# foo1.net
KiCad netlist of a schematic drawn in EAGLE
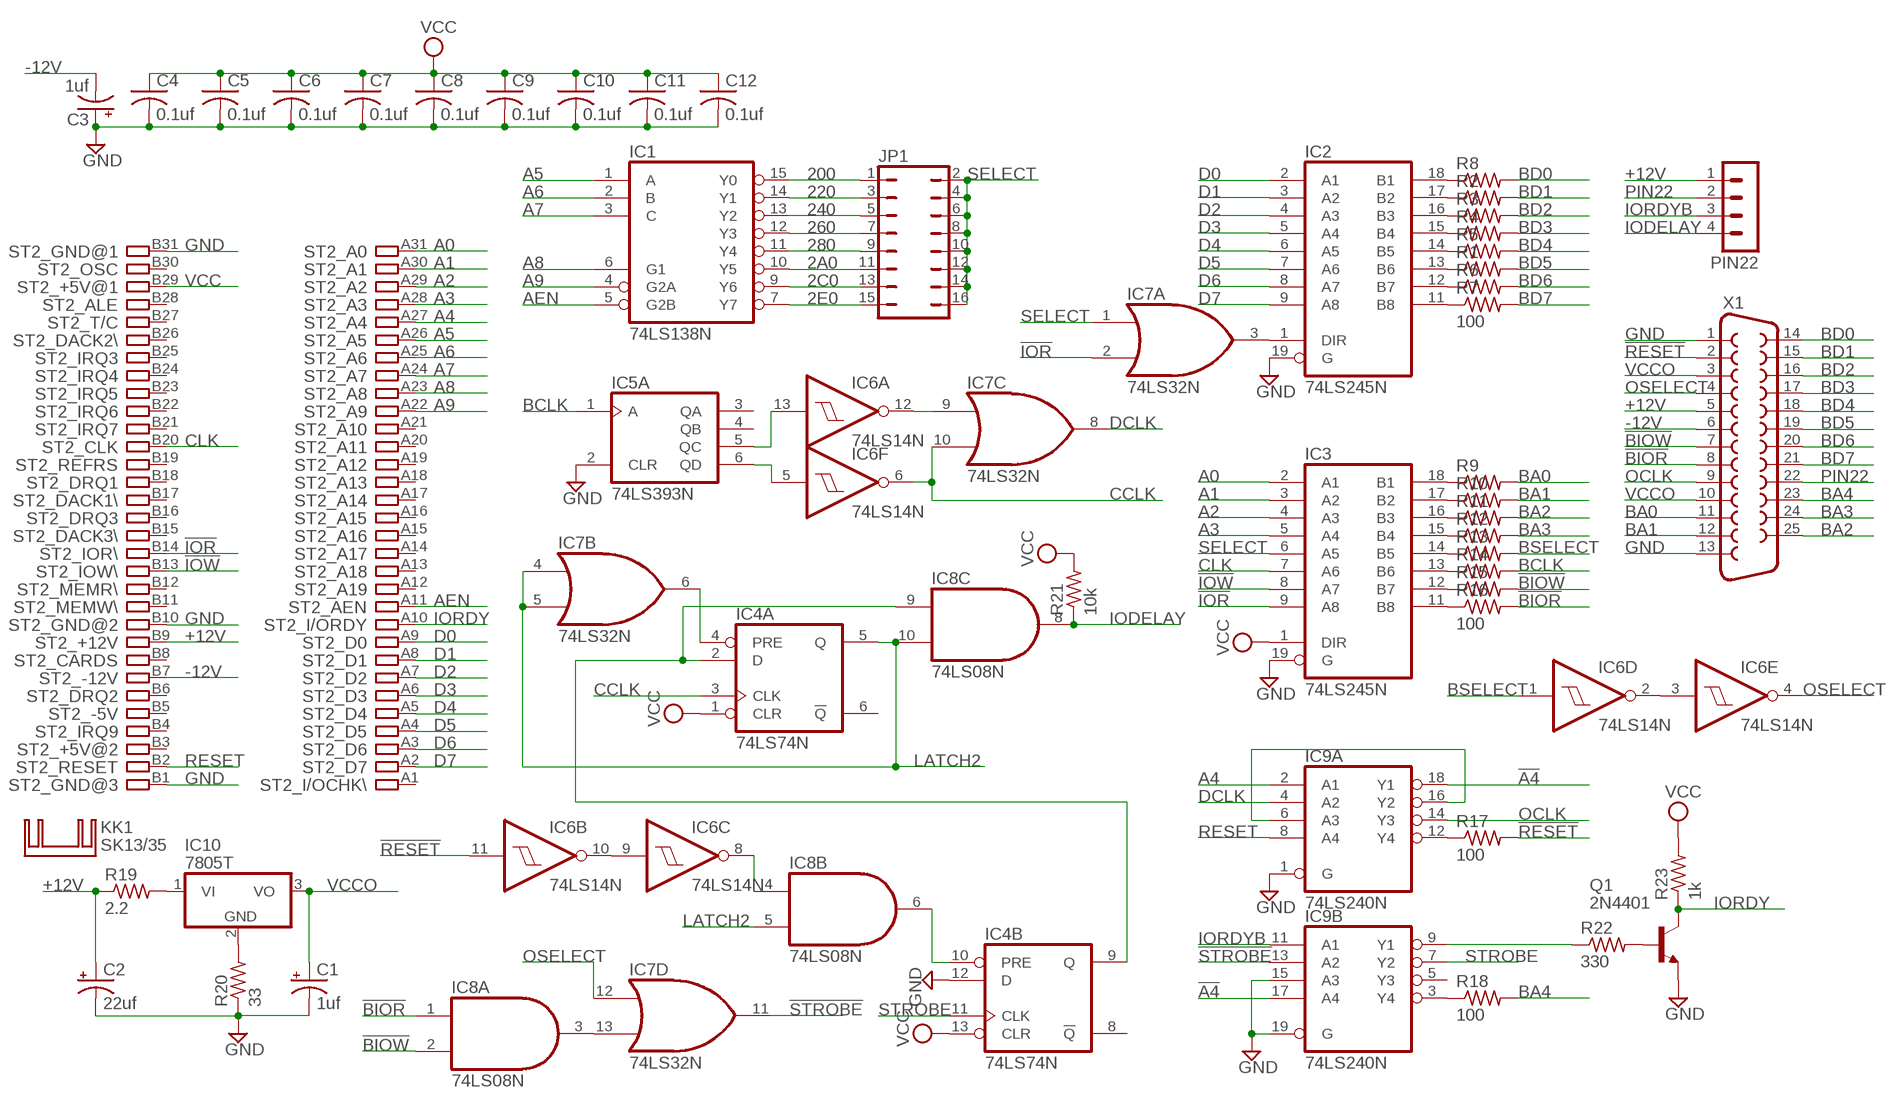
[diagram p0: schematic, sheet 1]

(export (version "E")
  (design (tool "Eeschema 10.0.6"))
  (components
    (comp (ref "C1")
      (value "1uf")
      (footprint "eagle-import:E5-10,5")
      (libsource (lib "eagle-import") (part "CPOL-USE5-10.5"))
    )
    (comp (ref "C2")
      (value "22uf")
      (footprint "eagle-import:E5-10,5")
      (libsource (lib "eagle-import") (part "CPOL-USE5-10.5"))
    )
    (comp (ref "C3")
      (value "1uf")
      (footprint "eagle-import:E5-10,5")
      (libsource (lib "eagle-import") (part "CPOL-USE5-10.5"))
    )
    (comp (ref "C4")
      (value "0.1uf")
      (footprint "eagle-import:C050-025X075")
      (libsource (lib "eagle-import") (part "C-US050-025X075"))
    )
    (comp (ref "C5")
      (value "0.1uf")
      (footprint "eagle-import:C050-025X075")
      (libsource (lib "eagle-import") (part "C-US050-025X075"))
    )
    (comp (ref "C6")
      (value "0.1uf")
      (footprint "eagle-import:C050-025X075")
      (libsource (lib "eagle-import") (part "C-US050-025X075"))
    )
    (comp (ref "C7")
      (value "0.1uf")
      (footprint "eagle-import:C050-025X075")
      (libsource (lib "eagle-import") (part "C-US050-025X075"))
    )
    (comp (ref "C8")
      (value "0.1uf")
      (footprint "eagle-import:C050-025X075")
      (libsource (lib "eagle-import") (part "C-US050-025X075"))
    )
    (comp (ref "C9")
      (value "0.1uf")
      (footprint "eagle-import:C050-025X075")
      (libsource (lib "eagle-import") (part "C-US050-025X075"))
    )
    (comp (ref "C10")
      (value "0.1uf")
      (footprint "eagle-import:C050-025X075")
      (libsource (lib "eagle-import") (part "C-US050-025X075"))
    )
    (comp (ref "C11")
      (value "0.1uf")
      (footprint "eagle-import:C050-025X075")
      (libsource (lib "eagle-import") (part "C-US050-025X075"))
    )
    (comp (ref "C12")
      (value "0.1uf")
      (footprint "eagle-import:C050-025X075")
      (libsource (lib "eagle-import") (part "C-US050-025X075"))
    )
    (comp (ref "IC1")
      (value "74LS138N")
      (footprint "eagle-import:DIL16")
      (libsource (lib "eagle-import") (part "74138NLS"))
    )
    (comp (ref "IC2")
      (value "74LS245N")
      (footprint "eagle-import:DIL20")
      (libsource (lib "eagle-import") (part "74245NLS"))
    )
    (comp (ref "IC3")
      (value "74LS245N")
      (footprint "eagle-import:DIL20")
      (libsource (lib "eagle-import") (part "74245NLS"))
    )
    (comp (ref "IC4")
      (value "74LS74N")
      (footprint "eagle-import:DIL14")
      (libsource (lib "eagle-import") (part "7474NLS"))
    )
    (comp (ref "IC5")
      (value "74LS393N")
      (footprint "eagle-import:DIL14")
      (libsource (lib "eagle-import") (part "74393NLS"))
    )
    (comp (ref "IC6")
      (value "74LS14N")
      (footprint "eagle-import:DIL14")
      (libsource (lib "eagle-import") (part "7414NLS"))
    )
    (comp (ref "IC7")
      (value "74LS32N")
      (footprint "eagle-import:DIL14")
      (libsource (lib "eagle-import") (part "7432NLS"))
    )
    (comp (ref "IC8")
      (value "74LS08N")
      (footprint "eagle-import:DIL14")
      (libsource (lib "eagle-import") (part "7408NLS"))
    )
    (comp (ref "IC9")
      (value "74LS240N")
      (footprint "eagle-import:DIL20")
      (libsource (lib "eagle-import") (part "74240NLS"))
    )
    (comp (ref "IC10")
      (value "7805T")
      (footprint "eagle-import:TO220H")
      (libsource (lib "eagle-import") (part "78T05"))
    )
    (comp (ref "JP1")
      (value "JP8Q")
      (footprint "eagle-import:JP8Q")
      (libsource (lib "eagle-import") (part "JP8Q"))
    )
    (comp (ref "KK1")
      (value "SK13/35")
      (footprint "eagle-import:SK13_35")
      (libsource (lib "eagle-import") (part "SK13/35"))
    )
    (comp (ref "PIN22")
      (value "MA04-1")
      (footprint "eagle-import:MA04-1")
      (libsource (lib "eagle-import") (part "MA04-1"))
    )
    (comp (ref "Q1")
      (value "2N4401")
      (footprint "eagle-import:TO92")
      (libsource (lib "eagle-import") (part "2N4416"))
    )
    (comp (ref "R1")
      (value "R-US_0207/10")
      (footprint "eagle-import:0207_10")
      (libsource (lib "eagle-import") (part "R-US_0207/10"))
    )
    (comp (ref "R2")
      (value "R-US_0207/10")
      (footprint "eagle-import:0207_10")
      (libsource (lib "eagle-import") (part "R-US_0207/10"))
    )
    (comp (ref "R3")
      (value "R-US_0207/10")
      (footprint "eagle-import:0207_10")
      (libsource (lib "eagle-import") (part "R-US_0207/10"))
    )
    (comp (ref "R4")
      (value "R-US_0207/10")
      (footprint "eagle-import:0207_10")
      (libsource (lib "eagle-import") (part "R-US_0207/10"))
    )
    (comp (ref "R5")
      (value "R-US_0207/10")
      (footprint "eagle-import:0207_10")
      (libsource (lib "eagle-import") (part "R-US_0207/10"))
    )
    (comp (ref "R6")
      (value "R-US_0207/10")
      (footprint "eagle-import:0207_10")
      (libsource (lib "eagle-import") (part "R-US_0207/10"))
    )
    (comp (ref "R7")
      (value "100")
      (footprint "eagle-import:0207_10")
      (libsource (lib "eagle-import") (part "R-US_0207/10"))
    )
    (comp (ref "R8")
      (value "R-US_0207/10")
      (footprint "eagle-import:0207_10")
      (libsource (lib "eagle-import") (part "R-US_0207/10"))
    )
    (comp (ref "R9")
      (value "R-US_0207/10")
      (footprint "eagle-import:0207_10")
      (libsource (lib "eagle-import") (part "R-US_0207/10"))
    )
    (comp (ref "R10")
      (value "R-US_0207/10")
      (footprint "eagle-import:0207_10")
      (libsource (lib "eagle-import") (part "R-US_0207/10"))
    )
    (comp (ref "R11")
      (value "R-US_0207/10")
      (footprint "eagle-import:0207_10")
      (libsource (lib "eagle-import") (part "R-US_0207/10"))
    )
    (comp (ref "R12")
      (value "R-US_0207/10")
      (footprint "eagle-import:0207_10")
      (libsource (lib "eagle-import") (part "R-US_0207/10"))
    )
    (comp (ref "R13")
      (value "R-US_0207/10")
      (footprint "eagle-import:0207_10")
      (libsource (lib "eagle-import") (part "R-US_0207/10"))
    )
    (comp (ref "R14")
      (value "R-US_0207/10")
      (footprint "eagle-import:0207_10")
      (libsource (lib "eagle-import") (part "R-US_0207/10"))
    )
    (comp (ref "R15")
      (value "R-US_0207/10")
      (footprint "eagle-import:0207_10")
      (libsource (lib "eagle-import") (part "R-US_0207/10"))
    )
    (comp (ref "R16")
      (value "100")
      (footprint "eagle-import:0207_10")
      (libsource (lib "eagle-import") (part "R-US_0207/10"))
    )
    (comp (ref "R17")
      (value "100")
      (footprint "eagle-import:0207_10")
      (libsource (lib "eagle-import") (part "R-US_0207/10"))
    )
    (comp (ref "R18")
      (value "100")
      (footprint "eagle-import:0207_10")
      (libsource (lib "eagle-import") (part "R-US_0207/10"))
    )
    (comp (ref "R19")
      (value "2.2")
      (footprint "eagle-import:P0613_15")
      (libsource (lib "eagle-import") (part "R-US_0613/15"))
    )
    (comp (ref "R20")
      (value "33")
      (footprint "eagle-import:0207_10")
      (libsource (lib "eagle-import") (part "R-US_0207/10"))
    )
    (comp (ref "R21")
      (value "10k")
      (footprint "eagle-import:0207_10")
      (libsource (lib "eagle-import") (part "R-US_0207/10"))
    )
    (comp (ref "R22")
      (value "330")
      (footprint "eagle-import:0207_10")
      (libsource (lib "eagle-import") (part "R-US_0207/10"))
    )
    (comp (ref "R23")
      (value "1k")
      (footprint "eagle-import:0207_10")
      (libsource (lib "eagle-import") (part "R-US_0207/10"))
    )
    (comp (ref "ST2")
      (value "IBM8BIT")
      (footprint "eagle-import:IBM8BIT")
      (libsource (lib "eagle-import") (part "IBM8BIT"))
    )
    (comp (ref "X1")
      (value "F25H")
      (footprint "eagle-import:F25H")
      (libsource (lib "eagle-import") (part "F25H"))
    )
  )
  (nets
    (net (code "1") (name "/+12V") (class "Default")
      (node (ref "C2") (pin "+") (pinfunction "+_+") (pintype "passive"))
      (node (ref "PIN22") (pin "1") (pinfunction "1_1") (pintype "passive"))
      (node (ref "R19") (pin "1") (pinfunction "1_1") (pintype "passive"))
      (node (ref "ST2") (pin "B9") (pinfunction "P_B9") (pintype "bidirectional"))
      (node (ref "X1") (pin "5") (pinfunction "5_5") (pintype "passive"))
    )
    (net (code "2") (name "/-12V") (class "Default")
      (node (ref "C3") (pin "-") (pinfunction "-_-") (pintype "passive"))
      (node (ref "ST2") (pin "B7") (pinfunction "P_B7") (pintype "bidirectional"))
      (node (ref "X1") (pin "6") (pinfunction "6_6") (pintype "passive"))
    )
    (net (code "3") (name "/2A0") (class "Default")
      (node (ref "IC1") (pin "10") (pinfunction "Y5_10") (pintype "output"))
      (node (ref "JP1") (pin "11") (pinfunction "11_11") (pintype "passive"))
    )
    (net (code "4") (name "/2C0") (class "Default")
      (node (ref "IC1") (pin "9") (pinfunction "Y6_9") (pintype "output"))
      (node (ref "JP1") (pin "13") (pinfunction "13_13") (pintype "passive"))
    )
    (net (code "5") (name "/2E0") (class "Default")
      (node (ref "IC1") (pin "7") (pinfunction "Y7_7") (pintype "output"))
      (node (ref "JP1") (pin "15") (pinfunction "15_15") (pintype "passive"))
    )
    (net (code "6") (name "/200") (class "Default")
      (node (ref "IC1") (pin "15") (pinfunction "Y0_15") (pintype "output"))
      (node (ref "JP1") (pin "1") (pinfunction "1_1") (pintype "passive"))
    )
    (net (code "7") (name "/220") (class "Default")
      (node (ref "IC1") (pin "14") (pinfunction "Y1_14") (pintype "output"))
      (node (ref "JP1") (pin "3") (pinfunction "3_3") (pintype "passive"))
    )
    (net (code "8") (name "/240") (class "Default")
      (node (ref "IC1") (pin "13") (pinfunction "Y2_13") (pintype "output"))
      (node (ref "JP1") (pin "5") (pinfunction "5_5") (pintype "passive"))
    )
    (net (code "9") (name "/260") (class "Default")
      (node (ref "IC1") (pin "12") (pinfunction "Y3_12") (pintype "output"))
      (node (ref "JP1") (pin "7") (pinfunction "7_7") (pintype "passive"))
    )
    (net (code "10") (name "/280") (class "Default")
      (node (ref "IC1") (pin "11") (pinfunction "Y4_11") (pintype "output"))
      (node (ref "JP1") (pin "9") (pinfunction "9_9") (pintype "passive"))
    )
    (net (code "11") (name "/A0") (class "Default")
      (node (ref "IC3") (pin "2") (pinfunction "A1_2") (pintype "bidirectional"))
      (node (ref "ST2") (pin "A31") (pinfunction "P_A31") (pintype "bidirectional"))
    )
    (net (code "12") (name "/A1") (class "Default")
      (node (ref "IC3") (pin "3") (pinfunction "A2_3") (pintype "bidirectional"))
      (node (ref "ST2") (pin "A30") (pinfunction "P_A30") (pintype "bidirectional"))
    )
    (net (code "13") (name "/A2") (class "Default")
      (node (ref "IC3") (pin "4") (pinfunction "A3_4") (pintype "bidirectional"))
      (node (ref "ST2") (pin "A29") (pinfunction "P_A29") (pintype "bidirectional"))
    )
    (net (code "14") (name "/A3") (class "Default")
      (node (ref "IC3") (pin "5") (pinfunction "A4_5") (pintype "bidirectional"))
      (node (ref "ST2") (pin "A28") (pinfunction "P_A28") (pintype "bidirectional"))
    )
    (net (code "15") (name "/A4") (class "Default")
      (node (ref "IC9") (pin "2") (pinfunction "A1_2") (pintype "input"))
      (node (ref "ST2") (pin "A27") (pinfunction "P_A27") (pintype "bidirectional"))
    )
    (net (code "16") (name "/A5") (class "Default")
      (node (ref "IC1") (pin "1") (pinfunction "A_1") (pintype "input"))
      (node (ref "ST2") (pin "A26") (pinfunction "P_A26") (pintype "bidirectional"))
    )
    (net (code "17") (name "/A6") (class "Default")
      (node (ref "IC1") (pin "2") (pinfunction "B_2") (pintype "input"))
      (node (ref "ST2") (pin "A25") (pinfunction "P_A25") (pintype "bidirectional"))
    )
    (net (code "18") (name "/A7") (class "Default")
      (node (ref "IC1") (pin "3") (pinfunction "C_3") (pintype "input"))
      (node (ref "ST2") (pin "A24") (pinfunction "P_A24") (pintype "bidirectional"))
    )
    (net (code "19") (name "/A8") (class "Default")
      (node (ref "IC1") (pin "6") (pinfunction "G1_6") (pintype "input"))
      (node (ref "ST2") (pin "A23") (pinfunction "P_A23") (pintype "bidirectional"))
    )
    (net (code "20") (name "/A9") (class "Default")
      (node (ref "IC1") (pin "4") (pinfunction "G2A_4") (pintype "input"))
      (node (ref "ST2") (pin "A22") (pinfunction "P_A22") (pintype "bidirectional"))
    )
    (net (code "21") (name "/AEN") (class "Default")
      (node (ref "IC1") (pin "5") (pinfunction "G2B_5") (pintype "input"))
      (node (ref "ST2") (pin "A11") (pinfunction "P_A11") (pintype "bidirectional"))
    )
    (net (code "22") (name "/BA0") (class "Default")
      (node (ref "R9") (pin "2") (pinfunction "2_2") (pintype "passive"))
      (node (ref "X1") (pin "11") (pinfunction "11_11") (pintype "passive"))
    )
    (net (code "23") (name "/BA1") (class "Default")
      (node (ref "R10") (pin "2") (pinfunction "2_2") (pintype "passive"))
      (node (ref "X1") (pin "12") (pinfunction "12_12") (pintype "passive"))
    )
    (net (code "24") (name "/BA2") (class "Default")
      (node (ref "R11") (pin "2") (pinfunction "2_2") (pintype "passive"))
      (node (ref "X1") (pin "25") (pinfunction "25_25") (pintype "passive"))
    )
    (net (code "25") (name "/BA3") (class "Default")
      (node (ref "R12") (pin "2") (pinfunction "2_2") (pintype "passive"))
      (node (ref "X1") (pin "24") (pinfunction "24_24") (pintype "passive"))
    )
    (net (code "26") (name "/BA4") (class "Default")
      (node (ref "R18") (pin "2") (pinfunction "2_2") (pintype "passive"))
      (node (ref "X1") (pin "23") (pinfunction "23_23") (pintype "passive"))
    )
    (net (code "27") (name "/BCLK") (class "Default")
      (node (ref "IC5") (pin "1") (pinfunction "A_1") (pintype "input"))
      (node (ref "R14") (pin "2") (pinfunction "2_2") (pintype "passive"))
    )
    (net (code "28") (name "/BD0") (class "Default")
      (node (ref "R8") (pin "2") (pinfunction "2_2") (pintype "passive"))
      (node (ref "X1") (pin "14") (pinfunction "14_14") (pintype "passive"))
    )
    (net (code "29") (name "/BD1") (class "Default")
      (node (ref "R2") (pin "2") (pinfunction "2_2") (pintype "passive"))
      (node (ref "X1") (pin "15") (pinfunction "15_15") (pintype "passive"))
    )
    (net (code "30") (name "/BD2") (class "Default")
      (node (ref "R3") (pin "2") (pinfunction "2_2") (pintype "passive"))
      (node (ref "X1") (pin "16") (pinfunction "16_16") (pintype "passive"))
    )
    (net (code "31") (name "/BD3") (class "Default")
      (node (ref "R4") (pin "2") (pinfunction "2_2") (pintype "passive"))
      (node (ref "X1") (pin "17") (pinfunction "17_17") (pintype "passive"))
    )
    (net (code "32") (name "/BD4") (class "Default")
      (node (ref "R5") (pin "2") (pinfunction "2_2") (pintype "passive"))
      (node (ref "X1") (pin "18") (pinfunction "18_18") (pintype "passive"))
    )
    (net (code "33") (name "/BD5") (class "Default")
      (node (ref "R1") (pin "2") (pinfunction "2_2") (pintype "passive"))
      (node (ref "X1") (pin "19") (pinfunction "19_19") (pintype "passive"))
    )
    (net (code "34") (name "/BD6") (class "Default")
      (node (ref "R6") (pin "2") (pinfunction "2_2") (pintype "passive"))
      (node (ref "X1") (pin "20") (pinfunction "20_20") (pintype "passive"))
    )
    (net (code "35") (name "/BD7") (class "Default")
      (node (ref "R7") (pin "2") (pinfunction "2_2") (pintype "passive"))
      (node (ref "X1") (pin "21") (pinfunction "21_21") (pintype "passive"))
    )
    (net (code "36") (name "/BSELECT") (class "Default")
      (node (ref "IC6") (pin "1") (pinfunction "I_1") (pintype "input"))
      (node (ref "R13") (pin "2") (pinfunction "2_2") (pintype "passive"))
    )
    (net (code "37") (name "/CCLK") (class "Default")
      (node (ref "IC4") (pin "3") (pinfunction "CLK_3") (pintype "input"))
      (node (ref "IC6") (pin "6") (pinfunction "O_6") (pintype "output"))
      (node (ref "IC7") (pin "10") (pinfunction "I1_10") (pintype "input"))
    )
    (net (code "38") (name "/CLK") (class "Default")
      (node (ref "IC3") (pin "7") (pinfunction "A6_7") (pintype "bidirectional"))
      (node (ref "ST2") (pin "B20") (pinfunction "P_B20") (pintype "bidirectional"))
    )
    (net (code "39") (name "/D0") (class "Default")
      (node (ref "IC2") (pin "2") (pinfunction "A1_2") (pintype "bidirectional"))
      (node (ref "ST2") (pin "A9") (pinfunction "P_A9") (pintype "bidirectional"))
    )
    (net (code "40") (name "/D1") (class "Default")
      (node (ref "IC2") (pin "3") (pinfunction "A2_3") (pintype "bidirectional"))
      (node (ref "ST2") (pin "A8") (pinfunction "P_A8") (pintype "bidirectional"))
    )
    (net (code "41") (name "/D2") (class "Default")
      (node (ref "IC2") (pin "4") (pinfunction "A3_4") (pintype "bidirectional"))
      (node (ref "ST2") (pin "A7") (pinfunction "P_A7") (pintype "bidirectional"))
    )
    (net (code "42") (name "/D3") (class "Default")
      (node (ref "IC2") (pin "5") (pinfunction "A4_5") (pintype "bidirectional"))
      (node (ref "ST2") (pin "A6") (pinfunction "P_A6") (pintype "bidirectional"))
    )
    (net (code "43") (name "/D4") (class "Default")
      (node (ref "IC2") (pin "6") (pinfunction "A5_6") (pintype "bidirectional"))
      (node (ref "ST2") (pin "A5") (pinfunction "P_A5") (pintype "bidirectional"))
    )
    (net (code "44") (name "/D5") (class "Default")
      (node (ref "IC2") (pin "7") (pinfunction "A6_7") (pintype "bidirectional"))
      (node (ref "ST2") (pin "A4") (pinfunction "P_A4") (pintype "bidirectional"))
    )
    (net (code "45") (name "/D6") (class "Default")
      (node (ref "IC2") (pin "8") (pinfunction "A7_8") (pintype "bidirectional"))
      (node (ref "ST2") (pin "A3") (pinfunction "P_A3") (pintype "bidirectional"))
    )
    (net (code "46") (name "/D7") (class "Default")
      (node (ref "IC2") (pin "9") (pinfunction "A8_9") (pintype "bidirectional"))
      (node (ref "ST2") (pin "A2") (pinfunction "P_A2") (pintype "bidirectional"))
    )
    (net (code "47") (name "/DCLK") (class "Default")
      (node (ref "IC7") (pin "8") (pinfunction "O_8") (pintype "output"))
      (node (ref "IC9") (pin "4") (pinfunction "A2_4") (pintype "input"))
    )
    (net (code "48") (name "/IODELAY") (class "Default")
      (node (ref "IC8") (pin "8") (pinfunction "O_8") (pintype "output"))
      (node (ref "PIN22") (pin "4") (pinfunction "4_4") (pintype "passive"))
      (node (ref "R21") (pin "1") (pinfunction "1_1") (pintype "passive"))
    )
    (net (code "49") (name "/IORDY") (class "Default")
      (node (ref "Q1") (pin "1") (pinfunction "C_1") (pintype "passive"))
      (node (ref "R23") (pin "1") (pinfunction "1_1") (pintype "passive"))
      (node (ref "ST2") (pin "A10") (pinfunction "P_A10") (pintype "bidirectional"))
    )
    (net (code "50") (name "/IORDYB") (class "Default")
      (node (ref "IC9") (pin "11") (pinfunction "A1_11") (pintype "input"))
      (node (ref "PIN22") (pin "3") (pinfunction "3_3") (pintype "passive"))
    )
    (net (code "51") (name "/LATCH2") (class "Default")
      (node (ref "IC4") (pin "5") (pinfunction "Q_5") (pintype "output"))
      (node (ref "IC7") (pin "4") (pinfunction "I0_4") (pintype "input"))
      (node (ref "IC7") (pin "5") (pinfunction "I1_5") (pintype "input"))
      (node (ref "IC8") (pin "10") (pinfunction "I1_10") (pintype "input"))
      (node (ref "IC8") (pin "5") (pinfunction "I1_5") (pintype "input"))
    )
    (net (code "52") (name "/OCLK") (class "Default")
      (node (ref "IC9") (pin "14") (pinfunction "Y3_14") (pintype "tri_state"))
      (node (ref "X1") (pin "9") (pinfunction "9_9") (pintype "passive"))
    )
    (net (code "53") (name "/OSELECT") (class "Default")
      (node (ref "IC6") (pin "4") (pinfunction "O_4") (pintype "output"))
      (node (ref "IC7") (pin "12") (pinfunction "I0_12") (pintype "input"))
      (node (ref "X1") (pin "4") (pinfunction "4_4") (pintype "passive"))
    )
    (net (code "54") (name "/PIN22") (class "Default")
      (node (ref "PIN22") (pin "2") (pinfunction "2_2") (pintype "passive"))
      (node (ref "X1") (pin "22") (pinfunction "22_22") (pintype "passive"))
    )
    (net (code "55") (name "/RESET") (class "Default")
      (node (ref "IC9") (pin "8") (pinfunction "A4_8") (pintype "input"))
      (node (ref "ST2") (pin "B2") (pinfunction "P_B2") (pintype "bidirectional"))
    )
    (net (code "56") (name "/SELECT") (class "Default")
      (node (ref "IC3") (pin "6") (pinfunction "A5_6") (pintype "bidirectional"))
      (node (ref "IC7") (pin "1") (pinfunction "I0_1") (pintype "input"))
      (node (ref "JP1") (pin "10") (pinfunction "10_10") (pintype "passive"))
      (node (ref "JP1") (pin "12") (pinfunction "12_12") (pintype "passive"))
      (node (ref "JP1") (pin "14") (pinfunction "14_14") (pintype "passive"))
      (node (ref "JP1") (pin "16") (pinfunction "16_16") (pintype "passive"))
      (node (ref "JP1") (pin "2") (pinfunction "2_2") (pintype "passive"))
      (node (ref "JP1") (pin "4") (pinfunction "4_4") (pintype "passive"))
      (node (ref "JP1") (pin "6") (pinfunction "6_6") (pintype "passive"))
      (node (ref "JP1") (pin "8") (pinfunction "8_8") (pintype "passive"))
    )
    (net (code "57") (name "/STROBE") (class "Default")
      (node (ref "IC4") (pin "11") (pinfunction "CLK_11") (pintype "input"))
      (node (ref "IC9") (pin "7") (pinfunction "Y2_7") (pintype "tri_state"))
    )
    (net (code "58") (name "/VCCO") (class "Default")
      (node (ref "C1") (pin "+") (pinfunction "+_+") (pintype "passive"))
      (node (ref "IC10") (pin "3") (pinfunction "VO_3") (pintype "passive"))
      (node (ref "X1") (pin "10") (pinfunction "10_10") (pintype "passive"))
      (node (ref "X1") (pin "3") (pinfunction "3_3") (pintype "passive"))
    )
    (net (code "59") (name "/~{A4}") (class "Default")
      (node (ref "IC9") (pin "17") (pinfunction "A4_17") (pintype "input"))
      (node (ref "IC9") (pin "18") (pinfunction "Y1_18") (pintype "tri_state"))
    )
    (net (code "60") (name "/~{BIOR}") (class "Default")
      (node (ref "IC8") (pin "1") (pinfunction "I0_1") (pintype "input"))
      (node (ref "R16") (pin "2") (pinfunction "2_2") (pintype "passive"))
      (node (ref "X1") (pin "8") (pinfunction "8_8") (pintype "passive"))
    )
    (net (code "61") (name "/~{BIOW}") (class "Default")
      (node (ref "IC8") (pin "2") (pinfunction "I1_2") (pintype "input"))
      (node (ref "R15") (pin "2") (pinfunction "2_2") (pintype "passive"))
      (node (ref "X1") (pin "7") (pinfunction "7_7") (pintype "passive"))
    )
    (net (code "62") (name "/~{IOR}") (class "Default")
      (node (ref "IC3") (pin "9") (pinfunction "A8_9") (pintype "bidirectional"))
      (node (ref "IC7") (pin "2") (pinfunction "I1_2") (pintype "input"))
      (node (ref "ST2") (pin "B14") (pinfunction "P_B14") (pintype "bidirectional"))
    )
    (net (code "63") (name "/~{IOW}") (class "Default")
      (node (ref "IC3") (pin "8") (pinfunction "A7_8") (pintype "bidirectional"))
      (node (ref "ST2") (pin "B13") (pinfunction "P_B13") (pintype "bidirectional"))
    )
    (net (code "64") (name "/~{RESET}") (class "Default")
      (node (ref "IC6") (pin "11") (pinfunction "I_11") (pintype "input"))
      (node (ref "R17") (pin "2") (pinfunction "2_2") (pintype "passive"))
      (node (ref "X1") (pin "2") (pinfunction "2_2") (pintype "passive"))
    )
    (net (code "65") (name "/~{STROBE}") (class "Default")
      (node (ref "IC7") (pin "11") (pinfunction "O_11") (pintype "output"))
      (node (ref "IC9") (pin "13") (pinfunction "A2_13") (pintype "input"))
    )
    (net (code "66") (name "GND") (class "Default")
      (node (ref "C1") (pin "-") (pinfunction "-_-") (pintype "passive"))
      (node (ref "C10") (pin "2") (pinfunction "2_2") (pintype "passive"))
      (node (ref "C11") (pin "2") (pinfunction "2_2") (pintype "passive"))
      (node (ref "C12") (pin "2") (pinfunction "2_2") (pintype "passive"))
      (node (ref "C2") (pin "-") (pinfunction "-_-") (pintype "passive"))
      (node (ref "C3") (pin "+") (pinfunction "+_+") (pintype "passive"))
      (node (ref "C4") (pin "2") (pinfunction "2_2") (pintype "passive"))
      (node (ref "C5") (pin "2") (pinfunction "2_2") (pintype "passive"))
      (node (ref "C6") (pin "2") (pinfunction "2_2") (pintype "passive"))
      (node (ref "C7") (pin "2") (pinfunction "2_2") (pintype "passive"))
      (node (ref "C8") (pin "2") (pinfunction "2_2") (pintype "passive"))
      (node (ref "C9") (pin "2") (pinfunction "2_2") (pintype "passive"))
      (node (ref "IC2") (pin "19") (pinfunction "G_19") (pintype "input"))
      (node (ref "IC3") (pin "19") (pinfunction "G_19") (pintype "input"))
      (node (ref "IC4") (pin "12") (pinfunction "D_12") (pintype "input"))
      (node (ref "IC5") (pin "2") (pinfunction "CLR_2") (pintype "input"))
      (node (ref "IC9") (pin "1") (pinfunction "G_1") (pintype "input"))
      (node (ref "IC9") (pin "15") (pinfunction "A3_15") (pintype "input"))
      (node (ref "IC9") (pin "19") (pinfunction "G_19") (pintype "input"))
      (node (ref "Q1") (pin "3") (pinfunction "E_3") (pintype "passive"))
      (node (ref "R20") (pin "1") (pinfunction "1_1") (pintype "passive"))
      (node (ref "ST2") (pin "B1") (pinfunction "P_B1") (pintype "bidirectional"))
      (node (ref "ST2") (pin "B10") (pinfunction "P_B10") (pintype "bidirectional"))
      (node (ref "ST2") (pin "B31") (pinfunction "P_B31") (pintype "bidirectional"))
      (node (ref "X1") (pin "1") (pinfunction "1_1") (pintype "passive"))
      (node (ref "X1") (pin "13") (pinfunction "13_13") (pintype "passive"))
    )
    (net (code "67") (name "Net-(IC2A-B1)") (class "Default")
      (node (ref "IC2") (pin "18") (pinfunction "B1_18") (pintype "bidirectional"))
      (node (ref "R8") (pin "1") (pinfunction "1_1") (pintype "passive"))
    )
    (net (code "68") (name "Net-(IC2A-B2)") (class "Default")
      (node (ref "IC2") (pin "17") (pinfunction "B2_17") (pintype "bidirectional"))
      (node (ref "R2") (pin "1") (pinfunction "1_1") (pintype "passive"))
    )
    (net (code "69") (name "Net-(IC2A-B3)") (class "Default")
      (node (ref "IC2") (pin "16") (pinfunction "B3_16") (pintype "bidirectional"))
      (node (ref "R3") (pin "1") (pinfunction "1_1") (pintype "passive"))
    )
    (net (code "70") (name "Net-(IC2A-B4)") (class "Default")
      (node (ref "IC2") (pin "15") (pinfunction "B4_15") (pintype "bidirectional"))
      (node (ref "R4") (pin "1") (pinfunction "1_1") (pintype "passive"))
    )
    (net (code "71") (name "Net-(IC2A-B5)") (class "Default")
      (node (ref "IC2") (pin "14") (pinfunction "B5_14") (pintype "bidirectional"))
      (node (ref "R5") (pin "1") (pinfunction "1_1") (pintype "passive"))
    )
    (net (code "72") (name "Net-(IC2A-B6)") (class "Default")
      (node (ref "IC2") (pin "13") (pinfunction "B6_13") (pintype "bidirectional"))
      (node (ref "R1") (pin "1") (pinfunction "1_1") (pintype "passive"))
    )
    (net (code "73") (name "Net-(IC2A-B7)") (class "Default")
      (node (ref "IC2") (pin "12") (pinfunction "B7_12") (pintype "bidirectional"))
      (node (ref "R6") (pin "1") (pinfunction "1_1") (pintype "passive"))
    )
    (net (code "74") (name "Net-(IC2A-B8)") (class "Default")
      (node (ref "IC2") (pin "11") (pinfunction "B8_11") (pintype "bidirectional"))
      (node (ref "R7") (pin "1") (pinfunction "1_1") (pintype "passive"))
    )
    (net (code "75") (name "Net-(IC2A-DIR)") (class "Default")
      (node (ref "IC2") (pin "1") (pinfunction "DIR_1") (pintype "input"))
      (node (ref "IC7") (pin "3") (pinfunction "O_3") (pintype "output"))
    )
    (net (code "76") (name "Net-(IC3A-B1)") (class "Default")
      (node (ref "IC3") (pin "18") (pinfunction "B1_18") (pintype "bidirectional"))
      (node (ref "R9") (pin "1") (pinfunction "1_1") (pintype "passive"))
    )
    (net (code "77") (name "Net-(IC3A-B2)") (class "Default")
      (node (ref "IC3") (pin "17") (pinfunction "B2_17") (pintype "bidirectional"))
      (node (ref "R10") (pin "1") (pinfunction "1_1") (pintype "passive"))
    )
    (net (code "78") (name "Net-(IC3A-B3)") (class "Default")
      (node (ref "IC3") (pin "16") (pinfunction "B3_16") (pintype "bidirectional"))
      (node (ref "R11") (pin "1") (pinfunction "1_1") (pintype "passive"))
    )
    (net (code "79") (name "Net-(IC3A-B4)") (class "Default")
      (node (ref "IC3") (pin "15") (pinfunction "B4_15") (pintype "bidirectional"))
      (node (ref "R12") (pin "1") (pinfunction "1_1") (pintype "passive"))
    )
    (net (code "80") (name "Net-(IC3A-B5)") (class "Default")
      (node (ref "IC3") (pin "14") (pinfunction "B5_14") (pintype "bidirectional"))
      (node (ref "R13") (pin "1") (pinfunction "1_1") (pintype "passive"))
    )
    (net (code "81") (name "Net-(IC3A-B6)") (class "Default")
      (node (ref "IC3") (pin "13") (pinfunction "B6_13") (pintype "bidirectional"))
      (node (ref "R14") (pin "1") (pinfunction "1_1") (pintype "passive"))
    )
    (net (code "82") (name "Net-(IC3A-B7)") (class "Default")
      (node (ref "IC3") (pin "12") (pinfunction "B7_12") (pintype "bidirectional"))
      (node (ref "R15") (pin "1") (pinfunction "1_1") (pintype "passive"))
    )
    (net (code "83") (name "Net-(IC3A-B8)") (class "Default")
      (node (ref "IC3") (pin "11") (pinfunction "B8_11") (pintype "bidirectional"))
      (node (ref "R16") (pin "1") (pinfunction "1_1") (pintype "passive"))
    )
    (net (code "84") (name "Net-(IC4A-D)") (class "Default")
      (node (ref "IC4") (pin "2") (pinfunction "D_2") (pintype "input"))
      (node (ref "IC4") (pin "9") (pinfunction "Q_9") (pintype "output"))
      (node (ref "IC8") (pin "9") (pinfunction "I0_9") (pintype "input"))
    )
    (net (code "85") (name "Net-(IC4A-PRE)") (class "Default")
      (node (ref "IC4") (pin "4") (pinfunction "PRE_4") (pintype "input"))
      (node (ref "IC7") (pin "6") (pinfunction "O_6") (pintype "output"))
    )
    (net (code "86") (name "Net-(IC4B-PRE)") (class "Default")
      (node (ref "IC4") (pin "10") (pinfunction "PRE_10") (pintype "input"))
      (node (ref "IC8") (pin "6") (pinfunction "O_6") (pintype "output"))
    )
    (net (code "87") (name "Net-(IC5A-QC)") (class "Default")
      (node (ref "IC5") (pin "5") (pinfunction "QC_5") (pintype "output"))
      (node (ref "IC6") (pin "13") (pinfunction "I_13") (pintype "input"))
    )
    (net (code "88") (name "Net-(IC5A-QD)") (class "Default")
      (node (ref "IC5") (pin "6") (pinfunction "QD_6") (pintype "output"))
      (node (ref "IC6") (pin "5") (pinfunction "I_5") (pintype "input"))
    )
    (net (code "89") (name "Net-(IC6A-O)") (class "Default")
      (node (ref "IC6") (pin "12") (pinfunction "O_12") (pintype "output"))
      (node (ref "IC7") (pin "9") (pinfunction "I0_9") (pintype "input"))
    )
    (net (code "90") (name "Net-(IC6B-O)") (class "Default")
      (node (ref "IC6") (pin "10") (pinfunction "O_10") (pintype "output"))
      (node (ref "IC6") (pin "9") (pinfunction "I_9") (pintype "input"))
    )
    (net (code "91") (name "Net-(IC6C-O)") (class "Default")
      (node (ref "IC6") (pin "8") (pinfunction "O_8") (pintype "output"))
      (node (ref "IC8") (pin "4") (pinfunction "I0_4") (pintype "input"))
    )
    (net (code "92") (name "Net-(IC6D-O)") (class "Default")
      (node (ref "IC6") (pin "2") (pinfunction "O_2") (pintype "output"))
      (node (ref "IC6") (pin "3") (pinfunction "I_3") (pintype "input"))
    )
    (net (code "93") (name "Net-(IC7D-I1)") (class "Default")
      (node (ref "IC7") (pin "13") (pinfunction "I1_13") (pintype "input"))
      (node (ref "IC8") (pin "3") (pinfunction "O_3") (pintype "output"))
    )
    (net (code "94") (name "Net-(IC9A-A3)") (class "Default")
      (node (ref "IC9") (pin "16") (pinfunction "Y2_16") (pintype "tri_state"))
      (node (ref "IC9") (pin "6") (pinfunction "A3_6") (pintype "input"))
    )
    (net (code "95") (name "Net-(IC9A-Y4)") (class "Default")
      (node (ref "IC9") (pin "12") (pinfunction "Y4_12") (pintype "tri_state"))
      (node (ref "R17") (pin "1") (pinfunction "1_1") (pintype "passive"))
    )
    (net (code "96") (name "Net-(IC9B-Y1)") (class "Default")
      (node (ref "IC9") (pin "9") (pinfunction "Y1_9") (pintype "tri_state"))
      (node (ref "R22") (pin "1") (pinfunction "1_1") (pintype "passive"))
    )
    (net (code "97") (name "Net-(IC9B-Y4)") (class "Default")
      (node (ref "IC9") (pin "3") (pinfunction "Y4_3") (pintype "tri_state"))
      (node (ref "R18") (pin "1") (pinfunction "1_1") (pintype "passive"))
    )
    (net (code "98") (name "Net-(IC10-GND)") (class "Default")
      (node (ref "IC10") (pin "2") (pinfunction "GND_2") (pintype "passive"))
      (node (ref "R20") (pin "2") (pinfunction "2_2") (pintype "passive"))
    )
    (net (code "99") (name "Net-(IC10-VI)") (class "Default")
      (node (ref "IC10") (pin "1") (pinfunction "VI_1") (pintype "input"))
      (node (ref "R19") (pin "2") (pinfunction "2_2") (pintype "passive"))
    )
    (net (code "100") (name "Net-(Q1-B)") (class "Default")
      (node (ref "Q1") (pin "2") (pinfunction "B_2") (pintype "passive"))
      (node (ref "R22") (pin "2") (pinfunction "2_2") (pintype "passive"))
    )
    (net (code "101") (name "VCC") (class "Default")
      (node (ref "C10") (pin "1") (pinfunction "1_1") (pintype "passive"))
      (node (ref "C11") (pin "1") (pinfunction "1_1") (pintype "passive"))
      (node (ref "C12") (pin "1") (pinfunction "1_1") (pintype "passive"))
      (node (ref "C4") (pin "1") (pinfunction "1_1") (pintype "passive"))
      (node (ref "C5") (pin "1") (pinfunction "1_1") (pintype "passive"))
      (node (ref "C6") (pin "1") (pinfunction "1_1") (pintype "passive"))
      (node (ref "C7") (pin "1") (pinfunction "1_1") (pintype "passive"))
      (node (ref "C8") (pin "1") (pinfunction "1_1") (pintype "passive"))
      (node (ref "C9") (pin "1") (pinfunction "1_1") (pintype "passive"))
      (node (ref "IC3") (pin "1") (pinfunction "DIR_1") (pintype "input"))
      (node (ref "IC4") (pin "1") (pinfunction "CLR_1") (pintype "input"))
      (node (ref "IC4") (pin "13") (pinfunction "CLR_13") (pintype "input"))
      (node (ref "R21") (pin "2") (pinfunction "2_2") (pintype "passive"))
      (node (ref "R23") (pin "2") (pinfunction "2_2") (pintype "passive"))
      (node (ref "ST2") (pin "B29") (pinfunction "P_B29") (pintype "bidirectional"))
    )
    (net (code "102") (name "unconnected-(IC4A-~{Q}-Pad6)") (class "Default")
      (node (ref "IC4") (pin "6") (pinfunction "~{Q}_6") (pintype "output"))
    )
    (net (code "103") (name "unconnected-(IC4B-~{Q}-Pad8)") (class "Default")
      (node (ref "IC4") (pin "8") (pinfunction "~{Q}_8") (pintype "output"))
    )
    (net (code "104") (name "unconnected-(IC5A-QA-Pad3)") (class "Default")
      (node (ref "IC5") (pin "3") (pinfunction "QA_3") (pintype "output"))
    )
    (net (code "105") (name "unconnected-(IC5A-QB-Pad4)") (class "Default")
      (node (ref "IC5") (pin "4") (pinfunction "QB_4") (pintype "output"))
    )
    (net (code "106") (name "unconnected-(IC9B-Y3-Pad5)") (class "Default")
      (node (ref "IC9") (pin "5") (pinfunction "Y3_5") (pintype "tri_state"))
    )
    (net (code "107") (name "unconnected-(ST2AA-P-PadB28)") (class "Default")
      (node (ref "ST2") (pin "B28") (pinfunction "P_B28") (pintype "bidirectional"))
    )
    (net (code "108") (name "unconnected-(ST2AB-P-PadB8)") (class "Default")
      (node (ref "ST2") (pin "B8") (pinfunction "P_B8") (pintype "bidirectional"))
    )
    (net (code "109") (name "unconnected-(ST2AL-P-PadB17)") (class "Default")
      (node (ref "ST2") (pin "B17") (pinfunction "P_B17") (pintype "bidirectional"))
    )
    (net (code "110") (name "unconnected-(ST2AM-P-PadB26)") (class "Default")
      (node (ref "ST2") (pin "B26") (pinfunction "P_B26") (pintype "bidirectional"))
    )
    (net (code "111") (name "unconnected-(ST2AN-P-PadB15)") (class "Default")
      (node (ref "ST2") (pin "B15") (pinfunction "P_B15") (pintype "bidirectional"))
    )
    (net (code "112") (name "unconnected-(ST2AO-P-PadB18)") (class "Default")
      (node (ref "ST2") (pin "B18") (pinfunction "P_B18") (pintype "bidirectional"))
    )
    (net (code "113") (name "unconnected-(ST2AP-P-PadB6)") (class "Default")
      (node (ref "ST2") (pin "B6") (pinfunction "P_B6") (pintype "bidirectional"))
    )
    (net (code "114") (name "unconnected-(ST2AQ-P-PadB16)") (class "Default")
      (node (ref "ST2") (pin "B16") (pinfunction "P_B16") (pintype "bidirectional"))
    )
    (net (code "115") (name "unconnected-(ST2AU-P-PadA1)") (class "Default")
      (node (ref "ST2") (pin "A1") (pinfunction "P_A1") (pintype "bidirectional"))
    )
    (net (code "116") (name "unconnected-(ST2AY-P-PadB25)") (class "Default")
      (node (ref "ST2") (pin "B25") (pinfunction "P_B25") (pintype "bidirectional"))
    )
    (net (code "117") (name "unconnected-(ST2AZ-P-PadB24)") (class "Default")
      (node (ref "ST2") (pin "B24") (pinfunction "P_B24") (pintype "bidirectional"))
    )
    (net (code "118") (name "unconnected-(ST2BA-P-PadB23)") (class "Default")
      (node (ref "ST2") (pin "B23") (pinfunction "P_B23") (pintype "bidirectional"))
    )
    (net (code "119") (name "unconnected-(ST2BB-P-PadB22)") (class "Default")
      (node (ref "ST2") (pin "B22") (pinfunction "P_B22") (pintype "bidirectional"))
    )
    (net (code "120") (name "unconnected-(ST2BC-P-PadB21)") (class "Default")
      (node (ref "ST2") (pin "B21") (pinfunction "P_B21") (pintype "bidirectional"))
    )
    (net (code "121") (name "unconnected-(ST2BD-P-PadB4)") (class "Default")
      (node (ref "ST2") (pin "B4") (pinfunction "P_B4") (pintype "bidirectional"))
    )
    (net (code "122") (name "unconnected-(ST2BE-P-PadB12)") (class "Default")
      (node (ref "ST2") (pin "B12") (pinfunction "P_B12") (pintype "bidirectional"))
    )
    (net (code "123") (name "unconnected-(ST2BF-P-PadB11)") (class "Default")
      (node (ref "ST2") (pin "B11") (pinfunction "P_B11") (pintype "bidirectional"))
    )
    (net (code "124") (name "unconnected-(ST2BG-P-PadB30)") (class "Default")
      (node (ref "ST2") (pin "B30") (pinfunction "P_B30") (pintype "bidirectional"))
    )
    (net (code "125") (name "unconnected-(ST2BH-P-PadB19)") (class "Default")
      (node (ref "ST2") (pin "B19") (pinfunction "P_B19") (pintype "bidirectional"))
    )
    (net (code "126") (name "unconnected-(ST2BJ-P-PadB27)") (class "Default")
      (node (ref "ST2") (pin "B27") (pinfunction "P_B27") (pintype "bidirectional"))
    )
    (net (code "127") (name "unconnected-(ST2C-P-PadB3)") (class "Default")
      (node (ref "ST2") (pin "B3") (pinfunction "P_B3") (pintype "bidirectional"))
    )
    (net (code "128") (name "unconnected-(ST2E-P-PadB5)") (class "Default")
      (node (ref "ST2") (pin "B5") (pinfunction "P_B5") (pintype "bidirectional"))
    )
    (net (code "129") (name "unconnected-(ST2H-P-PadA21)") (class "Default")
      (node (ref "ST2") (pin "A21") (pinfunction "P_A21") (pintype "bidirectional"))
    )
    (net (code "130") (name "unconnected-(ST2I-P-PadA20)") (class "Default")
      (node (ref "ST2") (pin "A20") (pinfunction "P_A20") (pintype "bidirectional"))
    )
    (net (code "131") (name "unconnected-(ST2J-P-PadA19)") (class "Default")
      (node (ref "ST2") (pin "A19") (pinfunction "P_A19") (pintype "bidirectional"))
    )
    (net (code "132") (name "unconnected-(ST2K-P-PadA18)") (class "Default")
      (node (ref "ST2") (pin "A18") (pinfunction "P_A18") (pintype "bidirectional"))
    )
    (net (code "133") (name "unconnected-(ST2L-P-PadA17)") (class "Default")
      (node (ref "ST2") (pin "A17") (pinfunction "P_A17") (pintype "bidirectional"))
    )
    (net (code "134") (name "unconnected-(ST2M-P-PadA16)") (class "Default")
      (node (ref "ST2") (pin "A16") (pinfunction "P_A16") (pintype "bidirectional"))
    )
    (net (code "135") (name "unconnected-(ST2N-P-PadA15)") (class "Default")
      (node (ref "ST2") (pin "A15") (pinfunction "P_A15") (pintype "bidirectional"))
    )
    (net (code "136") (name "unconnected-(ST2O-P-PadA14)") (class "Default")
      (node (ref "ST2") (pin "A14") (pinfunction "P_A14") (pintype "bidirectional"))
    )
    (net (code "137") (name "unconnected-(ST2P-P-PadA13)") (class "Default")
      (node (ref "ST2") (pin "A13") (pinfunction "P_A13") (pintype "bidirectional"))
    )
    (net (code "138") (name "unconnected-(ST2Q-P-PadA12)") (class "Default")
      (node (ref "ST2") (pin "A12") (pinfunction "P_A12") (pintype "bidirectional"))
    )
  )
)
